# power.net
KiCad netlist of a schematic drawn in EAGLE
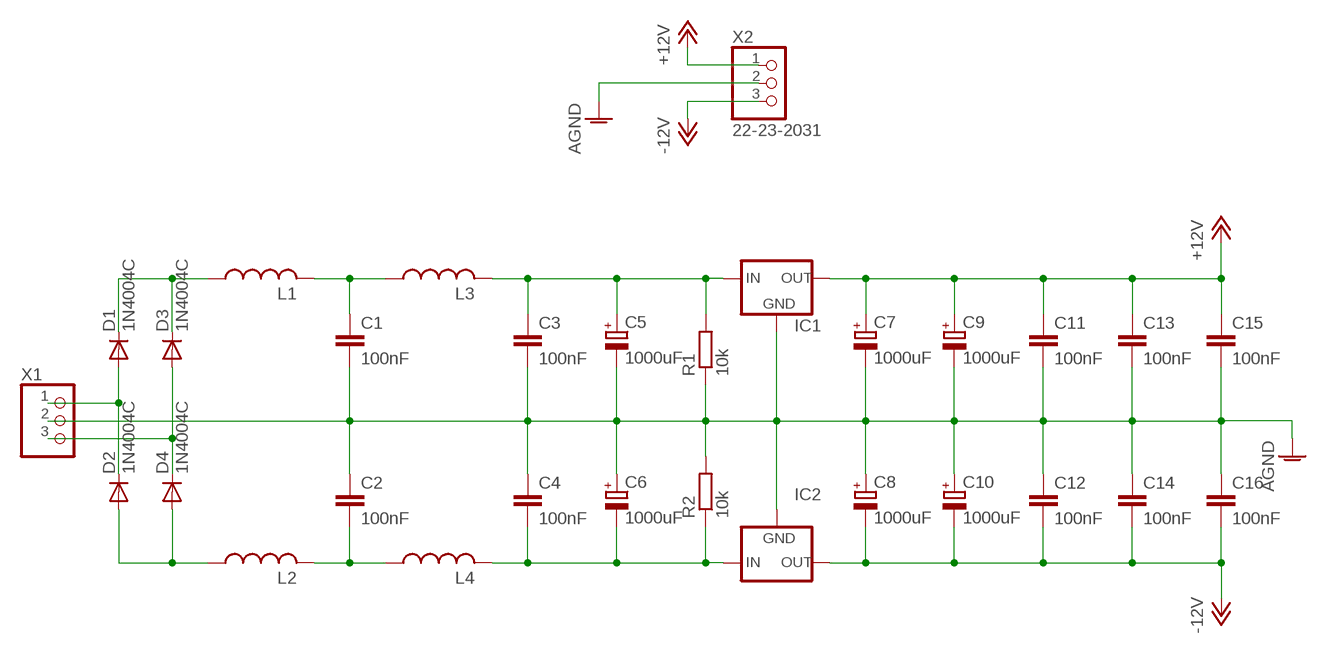
[diagram p0: schematic, sheet 1]

(export (version "E")
  (design (tool "Eeschema 10.0.6"))
  (components
    (comp (ref "C1")
      (value "100nF")
      (footprint "eagle-import:C050-045X075")
      (libsource (lib "eagle-import") (part "C-EU050-045X075"))
    )
    (comp (ref "C2")
      (value "100nF")
      (footprint "eagle-import:C050-045X075")
      (libsource (lib "eagle-import") (part "C-EU050-045X075"))
    )
    (comp (ref "C3")
      (value "100nF")
      (footprint "eagle-import:C050-045X075")
      (libsource (lib "eagle-import") (part "C-EU050-045X075"))
    )
    (comp (ref "C4")
      (value "100nF")
      (footprint "eagle-import:C050-045X075")
      (libsource (lib "eagle-import") (part "C-EU050-045X075"))
    )
    (comp (ref "C5")
      (value "1000uF")
      (footprint "eagle-import:E5-13")
      (libsource (lib "eagle-import") (part "CPOL-EUE5-13"))
    )
    (comp (ref "C6")
      (value "1000uF")
      (footprint "eagle-import:E5-13")
      (libsource (lib "eagle-import") (part "CPOL-EUE5-13"))
    )
    (comp (ref "C7")
      (value "1000uF")
      (footprint "eagle-import:E5-13")
      (libsource (lib "eagle-import") (part "CPOL-EUE5-13"))
    )
    (comp (ref "C8")
      (value "1000uF")
      (footprint "eagle-import:E5-13")
      (libsource (lib "eagle-import") (part "CPOL-EUE5-13"))
    )
    (comp (ref "C9")
      (value "1000uF")
      (footprint "eagle-import:E5-13")
      (libsource (lib "eagle-import") (part "CPOL-EUE5-13"))
    )
    (comp (ref "C10")
      (value "1000uF")
      (footprint "eagle-import:E5-13")
      (libsource (lib "eagle-import") (part "CPOL-EUE5-13"))
    )
    (comp (ref "C11")
      (value "100nF")
      (footprint "eagle-import:C050-045X075")
      (libsource (lib "eagle-import") (part "C-EU050-045X075"))
    )
    (comp (ref "C12")
      (value "100nF")
      (footprint "eagle-import:C050-045X075")
      (libsource (lib "eagle-import") (part "C-EU050-045X075"))
    )
    (comp (ref "C13")
      (value "100nF")
      (footprint "eagle-import:C050-045X075")
      (libsource (lib "eagle-import") (part "C-EU050-045X075"))
    )
    (comp (ref "C14")
      (value "100nF")
      (footprint "eagle-import:C050-045X075")
      (libsource (lib "eagle-import") (part "C-EU050-045X075"))
    )
    (comp (ref "C15")
      (value "100nF")
      (footprint "eagle-import:C050-045X075")
      (libsource (lib "eagle-import") (part "C-EU050-045X075"))
    )
    (comp (ref "C16")
      (value "100nF")
      (footprint "eagle-import:C050-045X075")
      (libsource (lib "eagle-import") (part "C-EU050-045X075"))
    )
    (comp (ref "D1")
      (value "1N4004C")
      (footprint "eagle-import:DO41-10")
      (libsource (lib "eagle-import") (part "1N4004C"))
    )
    (comp (ref "D2")
      (value "1N4004C")
      (footprint "eagle-import:DO41-10")
      (libsource (lib "eagle-import") (part "1N4004C"))
    )
    (comp (ref "D3")
      (value "1N4004C")
      (footprint "eagle-import:DO41-10")
      (libsource (lib "eagle-import") (part "1N4004C"))
    )
    (comp (ref "D4")
      (value "1N4004C")
      (footprint "eagle-import:DO41-10")
      (libsource (lib "eagle-import") (part "1N4004C"))
    )
    (comp (ref "IC1")
      (value "78XXTO-220")
      (footprint "eagle-import:78XXS")
      (libsource (lib "eagle-import") (part "78XXTO-220"))
    )
    (comp (ref "IC2")
      (value "79XXTO-220")
      (footprint "eagle-import:79XXS")
      (libsource (lib "eagle-import") (part "79XXTO-220"))
    )
    (comp (ref "L1")
      (value "L-US075-063X106")
      (footprint "eagle-import:L075-063X106")
      (libsource (lib "eagle-import") (part "L-US075-063X106"))
    )
    (comp (ref "L2")
      (value "L-US075-063X106")
      (footprint "eagle-import:L075-063X106")
      (libsource (lib "eagle-import") (part "L-US075-063X106"))
    )
    (comp (ref "L3")
      (value "L-US075-063X106")
      (footprint "eagle-import:L075-063X106")
      (libsource (lib "eagle-import") (part "L-US075-063X106"))
    )
    (comp (ref "L4")
      (value "L-US075-063X106")
      (footprint "eagle-import:L075-063X106")
      (libsource (lib "eagle-import") (part "L-US075-063X106"))
    )
    (comp (ref "R1")
      (value "10k")
      (footprint "eagle-import:0207_2V")
      (libsource (lib "eagle-import") (part "R-EU_0207/2V"))
    )
    (comp (ref "R2")
      (value "10k")
      (footprint "eagle-import:0207_2V")
      (libsource (lib "eagle-import") (part "R-EU_0207/2V"))
    )
    (comp (ref "X1")
      (value "W237-103")
      (footprint "eagle-import:W237-103")
      (libsource (lib "eagle-import") (part "W237-103"))
    )
    (comp (ref "X2")
      (value "22-23-2031")
      (footprint "eagle-import:22-23-2031")
      (libsource (lib "eagle-import") (part "22-23-2031"))
    )
  )
  (nets
    (net (code "1") (name "+12V") (class "Default")
      (node (ref "C11") (pin "1") (pinfunction "1_1") (pintype "passive"))
      (node (ref "C13") (pin "1") (pinfunction "1_1") (pintype "passive"))
      (node (ref "C15") (pin "1") (pinfunction "1_1") (pintype "passive"))
      (node (ref "C7") (pin "+") (pinfunction "+_+") (pintype "passive"))
      (node (ref "C9") (pin "+") (pinfunction "+_+") (pintype "passive"))
      (node (ref "IC1") (pin "OUT") (pinfunction "OUT_OUT") (pintype "passive"))
      (node (ref "X2") (pin "1") (pinfunction "1_1") (pintype "passive"))
    )
    (net (code "2") (name "-12V") (class "Default")
      (node (ref "C10") (pin "-") (pinfunction "-_-") (pintype "passive"))
      (node (ref "C12") (pin "2") (pinfunction "2_2") (pintype "passive"))
      (node (ref "C14") (pin "2") (pinfunction "2_2") (pintype "passive"))
      (node (ref "C16") (pin "2") (pinfunction "2_2") (pintype "passive"))
      (node (ref "C8") (pin "-") (pinfunction "-_-") (pintype "passive"))
      (node (ref "IC2") (pin "OUT") (pinfunction "OUT_OUT") (pintype "passive"))
      (node (ref "X2") (pin "3") (pinfunction "3_3") (pintype "passive"))
    )
    (net (code "3") (name "AGND") (class "Default")
      (node (ref "C1") (pin "2") (pinfunction "2_2") (pintype "passive"))
      (node (ref "C10") (pin "+") (pinfunction "+_+") (pintype "passive"))
      (node (ref "C11") (pin "2") (pinfunction "2_2") (pintype "passive"))
      (node (ref "C12") (pin "1") (pinfunction "1_1") (pintype "passive"))
      (node (ref "C13") (pin "2") (pinfunction "2_2") (pintype "passive"))
      (node (ref "C14") (pin "1") (pinfunction "1_1") (pintype "passive"))
      (node (ref "C15") (pin "2") (pinfunction "2_2") (pintype "passive"))
      (node (ref "C16") (pin "1") (pinfunction "1_1") (pintype "passive"))
      (node (ref "C2") (pin "1") (pinfunction "1_1") (pintype "passive"))
      (node (ref "C3") (pin "2") (pinfunction "2_2") (pintype "passive"))
      (node (ref "C4") (pin "1") (pinfunction "1_1") (pintype "passive"))
      (node (ref "C5") (pin "-") (pinfunction "-_-") (pintype "passive"))
      (node (ref "C6") (pin "+") (pinfunction "+_+") (pintype "passive"))
      (node (ref "C7") (pin "-") (pinfunction "-_-") (pintype "passive"))
      (node (ref "C8") (pin "+") (pinfunction "+_+") (pintype "passive"))
      (node (ref "C9") (pin "-") (pinfunction "-_-") (pintype "passive"))
      (node (ref "IC1") (pin "GND") (pinfunction "GND_GND") (pintype "input"))
      (node (ref "IC2") (pin "GND") (pinfunction "GND_GND") (pintype "input"))
      (node (ref "R1") (pin "1") (pinfunction "1_1") (pintype "passive"))
      (node (ref "R2") (pin "2") (pinfunction "2_2") (pintype "passive"))
      (node (ref "X1") (pin "2") (pinfunction "2_2") (pintype "passive"))
      (node (ref "X2") (pin "2") (pinfunction "2_2") (pintype "passive"))
    )
    (net (code "4") (name "Net-(C1-Pad1)") (class "Default")
      (node (ref "C1") (pin "1") (pinfunction "1_1") (pintype "passive"))
      (node (ref "L1") (pin "2") (pinfunction "2_2") (pintype "passive"))
      (node (ref "L3") (pin "1") (pinfunction "1_1") (pintype "passive"))
    )
    (net (code "5") (name "Net-(C2-Pad2)") (class "Default")
      (node (ref "C2") (pin "2") (pinfunction "2_2") (pintype "passive"))
      (node (ref "L2") (pin "2") (pinfunction "2_2") (pintype "passive"))
      (node (ref "L4") (pin "1") (pinfunction "1_1") (pintype "passive"))
    )
    (net (code "6") (name "Net-(C3-Pad1)") (class "Default")
      (node (ref "C3") (pin "1") (pinfunction "1_1") (pintype "passive"))
      (node (ref "C5") (pin "+") (pinfunction "+_+") (pintype "passive"))
      (node (ref "IC1") (pin "IN") (pinfunction "IN_IN") (pintype "input"))
      (node (ref "L3") (pin "2") (pinfunction "2_2") (pintype "passive"))
      (node (ref "R1") (pin "2") (pinfunction "2_2") (pintype "passive"))
    )
    (net (code "7") (name "Net-(C4-Pad2)") (class "Default")
      (node (ref "C4") (pin "2") (pinfunction "2_2") (pintype "passive"))
      (node (ref "C6") (pin "-") (pinfunction "-_-") (pintype "passive"))
      (node (ref "IC2") (pin "IN") (pinfunction "IN_IN") (pintype "input"))
      (node (ref "L4") (pin "2") (pinfunction "2_2") (pintype "passive"))
      (node (ref "R2") (pin "1") (pinfunction "1_1") (pintype "passive"))
    )
    (net (code "8") (name "Net-(D1-PadA)") (class "Default")
      (node (ref "D1") (pin "A") (pinfunction "A_A") (pintype "passive"))
      (node (ref "D2") (pin "C") (pinfunction "C_C") (pintype "passive"))
      (node (ref "X1") (pin "1") (pinfunction "1_1") (pintype "passive"))
    )
    (net (code "9") (name "Net-(D1-PadC)") (class "Default")
      (node (ref "D1") (pin "C") (pinfunction "C_C") (pintype "passive"))
      (node (ref "D3") (pin "C") (pinfunction "C_C") (pintype "passive"))
      (node (ref "L1") (pin "1") (pinfunction "1_1") (pintype "passive"))
    )
    (net (code "10") (name "Net-(D2-PadA)") (class "Default")
      (node (ref "D2") (pin "A") (pinfunction "A_A") (pintype "passive"))
      (node (ref "D4") (pin "A") (pinfunction "A_A") (pintype "passive"))
      (node (ref "L2") (pin "1") (pinfunction "1_1") (pintype "passive"))
    )
    (net (code "11") (name "Net-(D3-PadA)") (class "Default")
      (node (ref "D3") (pin "A") (pinfunction "A_A") (pintype "passive"))
      (node (ref "D4") (pin "C") (pinfunction "C_C") (pintype "passive"))
      (node (ref "X1") (pin "3") (pinfunction "3_3") (pintype "passive"))
    )
  )
)
